# TTL_to_RS485_Converter_V1_1.net
KiCad netlist of a schematic drawn in EasyEDA Pro
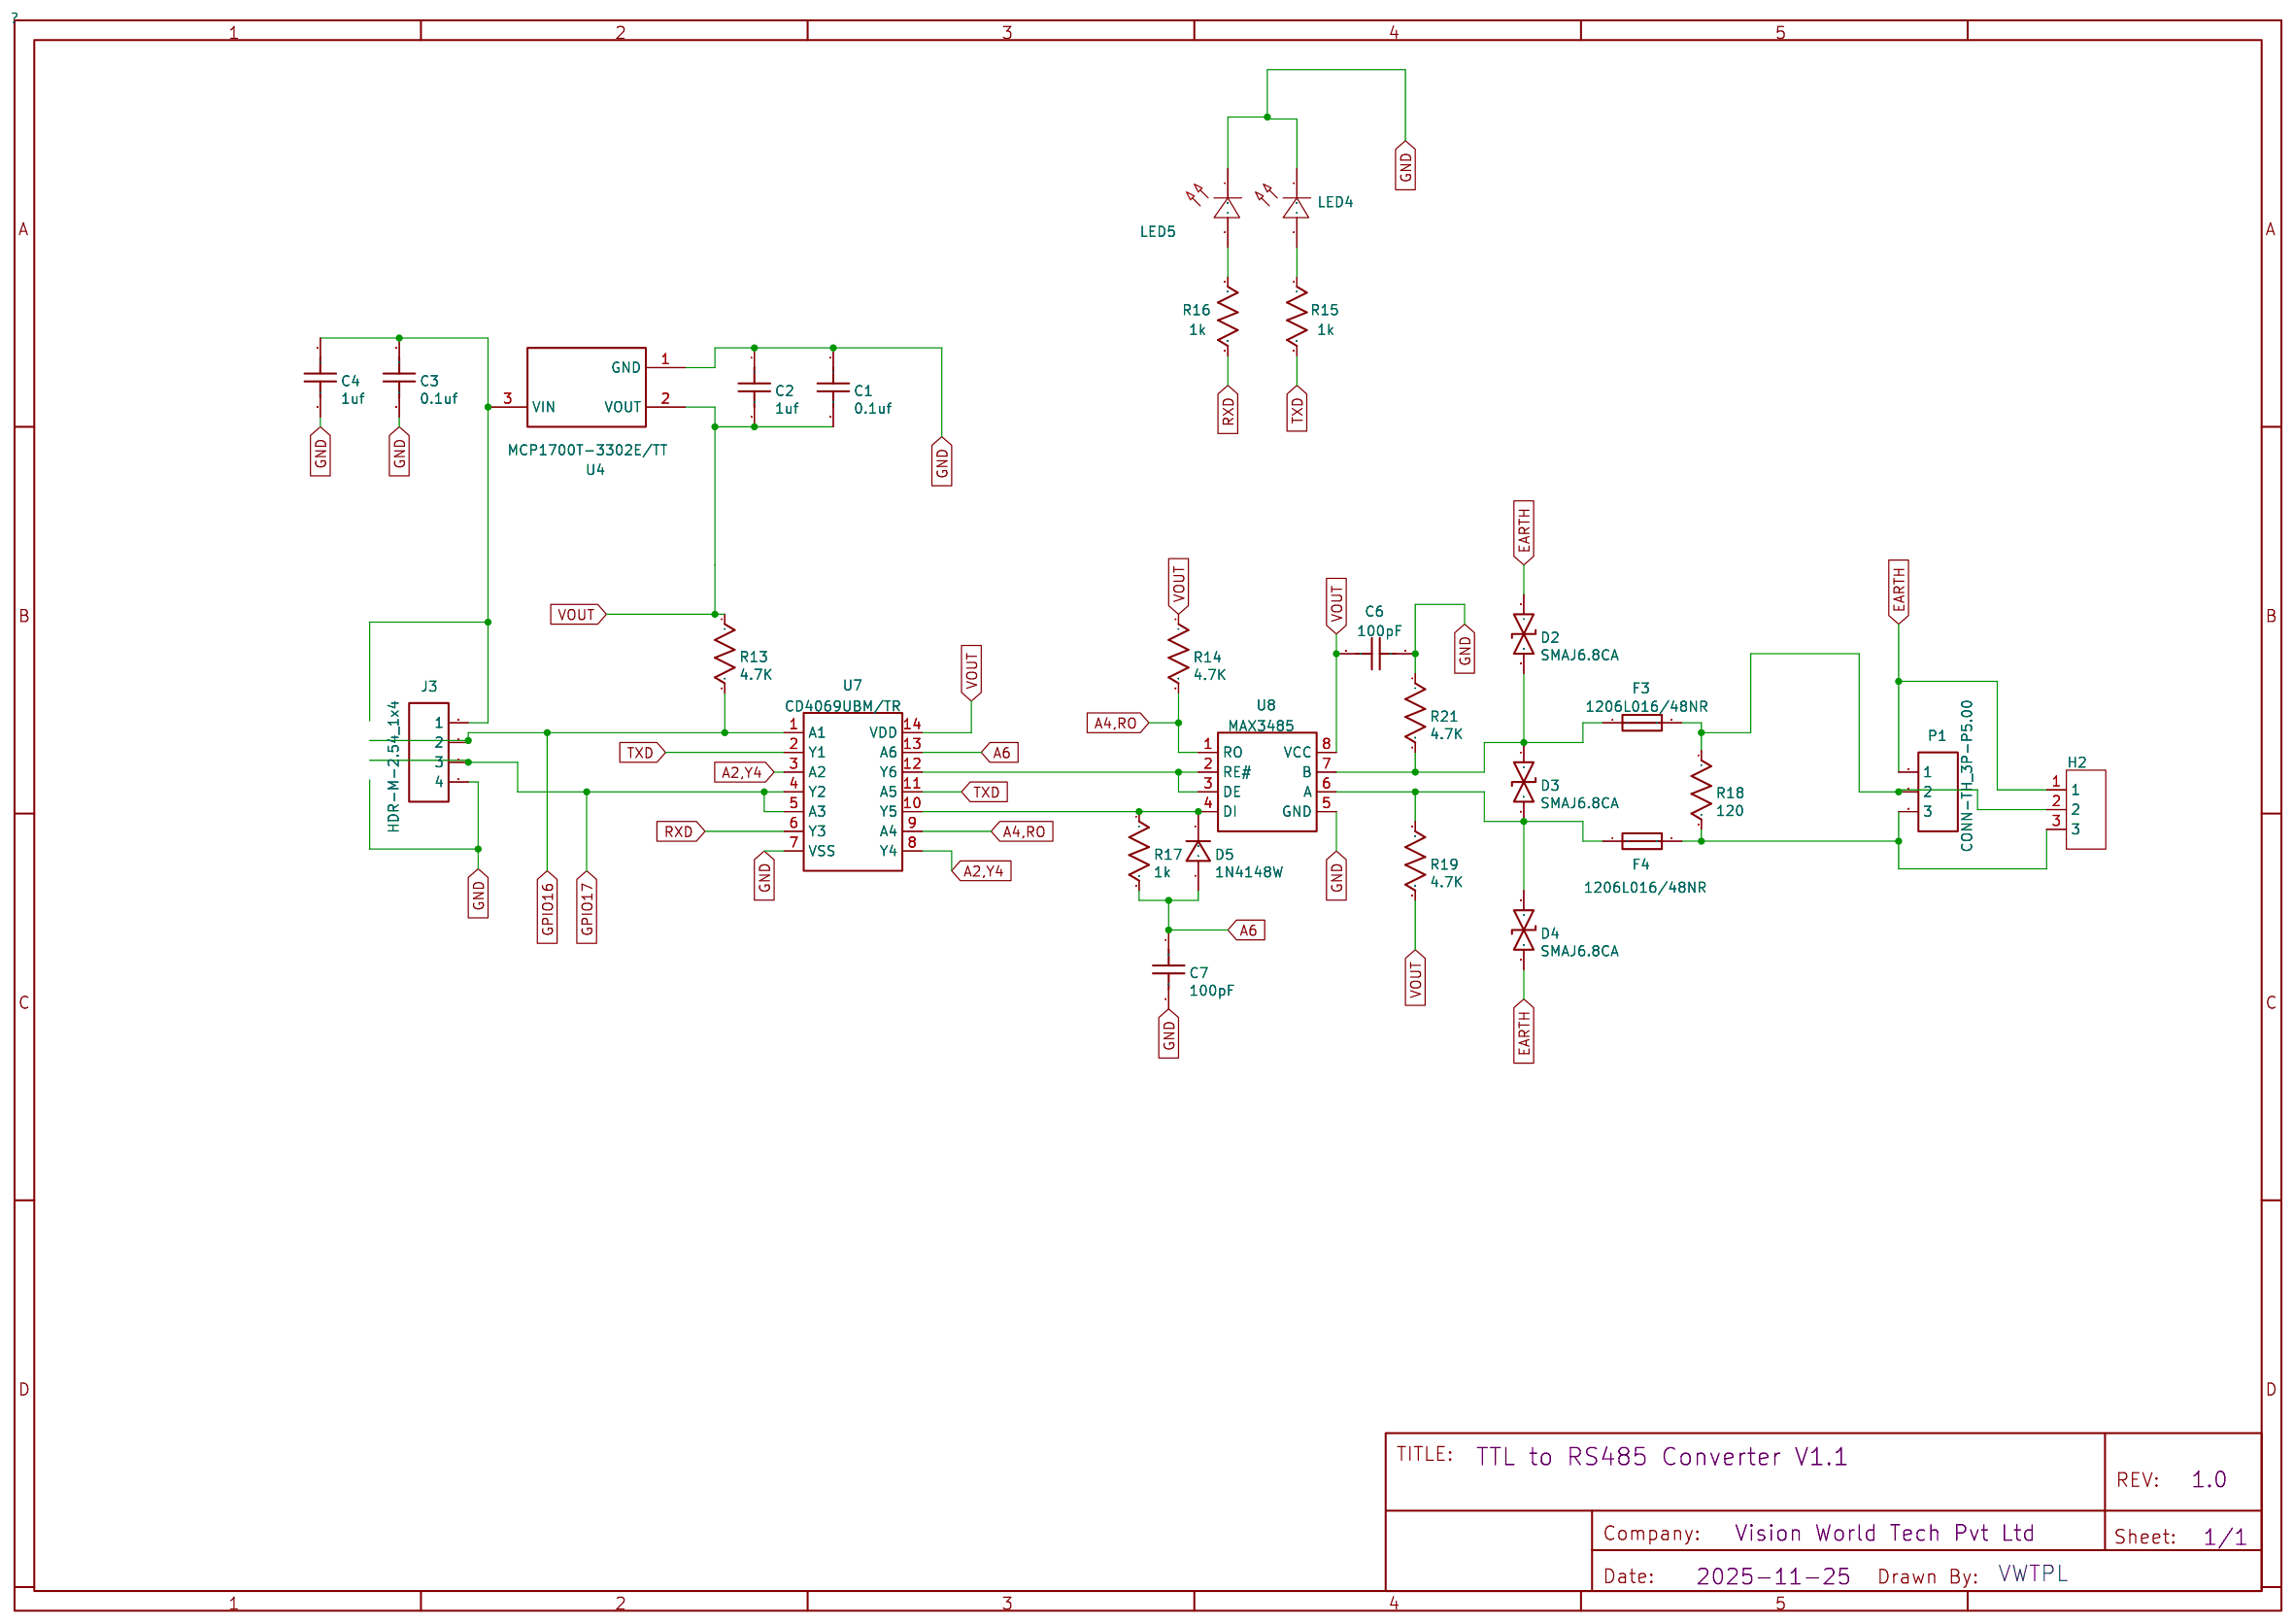
[diagram p0: schematic sheet]

(export (version "E")
  (design (tool "Eeschema 10.0.6"))
  (components
    (comp (ref "C1")
      (value "0.1uf")
      (footprint "easyedapro:C1206")
      (fields (field (name "Contributor") "LCEDA_Lib"))
      (libsource (lib "easyedapro") (part "0.1uf"))
    )
    (comp (ref "C2")
      (value "1uf")
      (footprint "easyedapro:C1206")
      (fields (field (name "Contributor") "LCEDA_Lib"))
      (libsource (lib "easyedapro") (part "1uf"))
    )
    (comp (ref "C3")
      (value "0.1uf")
      (footprint "easyedapro:C1206")
      (fields (field (name "Contributor") "LCEDA_Lib"))
      (libsource (lib "easyedapro") (part "0.1uf"))
    )
    (comp (ref "C4")
      (value "1uf")
      (footprint "easyedapro:C1206")
      (fields (field (name "Contributor") "LCEDA_Lib"))
      (libsource (lib "easyedapro") (part "1uf"))
    )
    (comp (ref "C6")
      (value "100pF")
      (footprint "easyedapro:C1206")
      (fields (field (name "Contributor") "LCEDA_Lib"))
      (libsource (lib "easyedapro") (part "100pF"))
    )
    (comp (ref "C7")
      (value "100pF")
      (footprint "easyedapro:C1206")
      (fields (field (name "Contributor") "LCEDA_Lib"))
      (libsource (lib "easyedapro") (part "100pF"))
    )
    (comp (ref "D2")
      (value "SMAJ6.8CA")
      (footprint "easyedapro:SMA_L4.4-W2.6-LS5.0-BI")
      (fields (field (name "Manufacturer") "BORN(伯恩半导体)") (field (name "Contributor") "LCSC"))
      (libsource (lib "easyedapro") (part "SMAJ6.8CA"))
    )
    (comp (ref "D3")
      (value "SMAJ6.8CA")
      (footprint "easyedapro:SMA_L4.4-W2.6-LS5.0-BI")
      (fields (field (name "Manufacturer") "BORN(伯恩半导体)") (field (name "Contributor") "LCSC"))
      (libsource (lib "easyedapro") (part "SMAJ6.8CA"))
    )
    (comp (ref "D4")
      (value "SMAJ6.8CA")
      (footprint "easyedapro:SMA_L4.4-W2.6-LS5.0-BI")
      (fields (field (name "Manufacturer") "BORN(伯恩半导体)") (field (name "Contributor") "LCSC"))
      (libsource (lib "easyedapro") (part "SMAJ6.8CA"))
    )
    (comp (ref "D5")
      (value "1N4148W")
      (footprint "easyedapro:SOD-123FL_L2.6-W1.6-LS3.4-RD")
      (fields (field (name "Manufacturer") "Tak Cheong") (field (name "Contributor") "LCEDA_Lib"))
      (libsource (lib "easyedapro") (part "1N4148W"))
    )
    (comp (ref "F3")
      (value "1206L016/48NR")
      (footprint "easyedapro:FUSE-SMD_1206L016-48NR")
      (fields (field (name "Manufacturer") "LUTE(陆特)") (field (name "Contributor") "lcsc"))
      (libsource (lib "easyedapro") (part "1206L016/48NR"))
    )
    (comp (ref "F4")
      (value "1206L016/48NR")
      (footprint "easyedapro:FUSE-SMD_1206L016-48NR")
      (fields (field (name "Manufacturer") "LUTE(陆特)") (field (name "Contributor") "lcsc"))
      (libsource (lib "easyedapro") (part "1206L016/48NR"))
    )
    (comp (ref "H2")
      (value "~")
      (footprint "easyedapro:HDR-TH_3P-P2.54-V-M")
      (libsource (lib "easyedapro") (part "PZ254V-11-03P_C2937625"))
    )
    (comp (ref "J3")
      (value "HDR-M-2.54_1x4")
      (footprint "easyedapro:HDR-M-2.54_1X4")
      (fields (field (name "Contributor") "LCEDA_Lib"))
      (libsource (lib "easyedapro") (part "HDR-M-2.54_1x4"))
    )
    (comp (ref "LED4")
      (value "~")
      (footprint "easyedapro:LED0805-RD_GREEN")
      (libsource (lib "easyedapro") (part "LED_B"))
    )
    (comp (ref "LED5")
      (value "~")
      (footprint "easyedapro:LED0805-RD_GREEN")
      (libsource (lib "easyedapro") (part "LED_G"))
    )
    (comp (ref "P1")
      (value "CONN-TH_3P-P5.00")
      (footprint "easyedapro:CONN-TH_3P-P5.00")
      (fields (field (name "Contributor") "LCEDA_Lib"))
      (libsource (lib "easyedapro") (part "CONN-TH_3P-P5.00"))
    )
    (comp (ref "R13")
      (value "4.7K")
      (footprint "easyedapro:R1206")
      (fields (field (name "Contributor") "LCEDA_Lib"))
      (libsource (lib "easyedapro") (part "4.7K"))
    )
    (comp (ref "R14")
      (value "4.7K")
      (footprint "easyedapro:R1206")
      (fields (field (name "Contributor") "LCEDA_Lib"))
      (libsource (lib "easyedapro") (part "4.7K"))
    )
    (comp (ref "R15")
      (value "1k")
      (footprint "easyedapro:R1206")
      (fields (field (name "Contributor") "LCEDA_Lib"))
      (libsource (lib "easyedapro") (part "1k"))
    )
    (comp (ref "R16")
      (value "1k")
      (footprint "easyedapro:R1206")
      (fields (field (name "Contributor") "LCEDA_Lib"))
      (libsource (lib "easyedapro") (part "1k"))
    )
    (comp (ref "R17")
      (value "1k")
      (footprint "easyedapro:R1206")
      (fields (field (name "Contributor") "LCEDA_Lib"))
      (libsource (lib "easyedapro") (part "1k"))
    )
    (comp (ref "R18")
      (value "120")
      (footprint "easyedapro:R1206")
      (fields (field (name "Contributor") "LCEDA_Lib"))
      (libsource (lib "easyedapro") (part "120"))
    )
    (comp (ref "R19")
      (value "4.7K")
      (footprint "easyedapro:R1206")
      (fields (field (name "Contributor") "LCEDA_Lib"))
      (libsource (lib "easyedapro") (part "4.7K"))
    )
    (comp (ref "R21")
      (value "4.7K")
      (footprint "easyedapro:R1206")
      (fields (field (name "Contributor") "LCEDA_Lib"))
      (libsource (lib "easyedapro") (part "4.7K"))
    )
    (comp (ref "U4")
      (value "MCP1700T-3302E/TT")
      (footprint "easyedapro:MCP1700-SOT-23-3_L2.9-W1.6-P1.90-LS2.8-BR")
      (fields (field (name "Manufacturer") "MICROCHIP") (field (name "Contributor") "Lavar Technologies"))
      (libsource (lib "easyedapro") (part "MCP1700T-3302E/TT"))
    )
    (comp (ref "U7")
      (value "CD4069UBM/TR")
      (footprint "easyedapro:SOIC-14_L8.7-W3.9-P1.27-LS6.0-BL")
      (fields (field (name "Manufacturer") "HGSEMI(华冠)") (field (name "Contributor") "LCSC"))
      (libsource (lib "easyedapro") (part "CD4069UBM/TR"))
    )
    (comp (ref "U8")
      (value "MAX3485")
      (footprint "easyedapro:SOP-8_L4.9-W3.9-P1.27-LS6.0-BL")
      (fields
        (field (name "Manufacturer Part") "MAX3485EIM/TR(ES)")
        (field (name "Manufacturer") "ElecSuper(静芯微)")
        (field (name "Contributor") "lcsc")
      )
      (libsource (lib "easyedapro") (part "MAX3485"))
    )
  )
  (nets
    (net (code "1") (name "A2,Y4") (class "Default")
      (node (ref "U7") (pin "3") (pinfunction "A2_3") (pintype "unspecified"))
      (node (ref "U7") (pin "8") (pinfunction "Y4_8") (pintype "unspecified"))
    )
    (net (code "2") (name "A4,RO") (class "Default")
      (node (ref "R14") (pin "2") (pinfunction "2_2") (pintype "unspecified"))
      (node (ref "U7") (pin "9") (pinfunction "A4_9") (pintype "unspecified"))
      (node (ref "U8") (pin "1") (pinfunction "RO_1") (pintype "unspecified"))
    )
    (net (code "3") (name "A6") (class "Default")
      (node (ref "C7") (pin "1") (pinfunction "1_1") (pintype "unspecified"))
      (node (ref "D5") (pin "2") (pinfunction "2_2") (pintype "unspecified"))
      (node (ref "R17") (pin "2") (pinfunction "2_2") (pintype "unspecified"))
      (node (ref "U7") (pin "13") (pinfunction "A6_13") (pintype "unspecified"))
    )
    (net (code "4") (name "EARTH") (class "Default")
      (node (ref "D2") (pin "1") (pinfunction "1_1") (pintype "unspecified"))
      (node (ref "D4") (pin "2") (pinfunction "2_2") (pintype "unspecified"))
      (node (ref "H2") (pin "1") (pinfunction "1_1") (pintype "unspecified"))
      (node (ref "P1") (pin "1") (pinfunction "1_1") (pintype "unspecified"))
    )
    (net (code "5") (name "GND") (class "Default")
      (node (ref "C1") (pin "1") (pinfunction "1_1") (pintype "unspecified"))
      (node (ref "C2") (pin "1") (pinfunction "1_1") (pintype "unspecified"))
      (node (ref "C3") (pin "2") (pinfunction "2_2") (pintype "unspecified"))
      (node (ref "C4") (pin "2") (pinfunction "2_2") (pintype "unspecified"))
      (node (ref "C6") (pin "1") (pinfunction "1_1") (pintype "unspecified"))
      (node (ref "C7") (pin "2") (pinfunction "2_2") (pintype "unspecified"))
      (node (ref "J3") (pin "4") (pinfunction "4_4") (pintype "unspecified"))
      (node (ref "LED4") (pin "1") (pinfunction "C_1") (pintype "input"))
      (node (ref "LED5") (pin "1") (pinfunction "C_1") (pintype "input"))
      (node (ref "R21") (pin "1") (pinfunction "1_1") (pintype "unspecified"))
      (node (ref "U4") (pin "1") (pinfunction "GND_1") (pintype "unspecified"))
      (node (ref "U7") (pin "7") (pinfunction "VSS_7") (pintype "unspecified"))
      (node (ref "U8") (pin "5") (pinfunction "GND_5") (pintype "unspecified"))
    )
    (net (code "6") (name "GPIO16") (class "Default")
      (node (ref "J3") (pin "2") (pinfunction "2_2") (pintype "unspecified"))
      (node (ref "R13") (pin "2") (pinfunction "2_2") (pintype "unspecified"))
      (node (ref "U7") (pin "1") (pinfunction "A1_1") (pintype "unspecified"))
    )
    (net (code "7") (name "GPIO17") (class "Default")
      (node (ref "J3") (pin "3") (pinfunction "3_3") (pintype "unspecified"))
      (node (ref "U7") (pin "4") (pinfunction "Y2_4") (pintype "unspecified"))
      (node (ref "U7") (pin "5") (pinfunction "A3_5") (pintype "unspecified"))
    )
    (net (code "8") (name "Net-(F3-Pad2)") (class "Default")
      (node (ref "F3") (pin "2") (pinfunction "2_2") (pintype "unspecified"))
      (node (ref "H2") (pin "2") (pinfunction "2_2") (pintype "unspecified"))
      (node (ref "P1") (pin "2") (pinfunction "2_2") (pintype "unspecified"))
      (node (ref "R18") (pin "1") (pinfunction "1_1") (pintype "unspecified"))
    )
    (net (code "9") (name "Net-(F4-Pad2)") (class "Default")
      (node (ref "F4") (pin "2") (pinfunction "2_2") (pintype "unspecified"))
      (node (ref "H2") (pin "3") (pinfunction "3_3") (pintype "unspecified"))
      (node (ref "P1") (pin "3") (pinfunction "3_3") (pintype "unspecified"))
      (node (ref "R18") (pin "2") (pinfunction "2_2") (pintype "unspecified"))
    )
    (net (code "10") (name "Net-(LED4-A)") (class "Default")
      (node (ref "LED4") (pin "2") (pinfunction "A_2") (pintype "input"))
      (node (ref "R15") (pin "1") (pinfunction "1_1") (pintype "unspecified"))
    )
    (net (code "11") (name "Net-(LED5-A)") (class "Default")
      (node (ref "LED5") (pin "2") (pinfunction "A_2") (pintype "input"))
      (node (ref "R16") (pin "1") (pinfunction "1_1") (pintype "unspecified"))
    )
    (net (code "12") (name "Net-(U4-VIN)") (class "Default")
      (node (ref "C3") (pin "1") (pinfunction "1_1") (pintype "unspecified"))
      (node (ref "C4") (pin "1") (pinfunction "1_1") (pintype "unspecified"))
      (node (ref "J3") (pin "1") (pinfunction "1_1") (pintype "unspecified"))
      (node (ref "U4") (pin "3") (pinfunction "VIN_3") (pintype "unspecified"))
    )
    (net (code "13") (name "Net-(U7-Y5)") (class "Default")
      (node (ref "D5") (pin "1") (pinfunction "1_1") (pintype "unspecified"))
      (node (ref "R17") (pin "1") (pinfunction "1_1") (pintype "unspecified"))
      (node (ref "U7") (pin "10") (pinfunction "Y5_10") (pintype "unspecified"))
      (node (ref "U8") (pin "4") (pinfunction "DI_4") (pintype "unspecified"))
    )
    (net (code "14") (name "Net-(U7-Y6)") (class "Default")
      (node (ref "U7") (pin "12") (pinfunction "Y6_12") (pintype "unspecified"))
      (node (ref "U8") (pin "2") (pinfunction "RE#_2") (pintype "unspecified"))
      (node (ref "U8") (pin "3") (pinfunction "DE_3") (pintype "unspecified"))
    )
    (net (code "15") (name "Net-(U8-A)") (class "Default")
      (node (ref "D3") (pin "2") (pinfunction "2_2") (pintype "unspecified"))
      (node (ref "D4") (pin "1") (pinfunction "1_1") (pintype "unspecified"))
      (node (ref "F4") (pin "1") (pinfunction "1_1") (pintype "unspecified"))
      (node (ref "R19") (pin "1") (pinfunction "1_1") (pintype "unspecified"))
      (node (ref "U8") (pin "6") (pinfunction "A_6") (pintype "unspecified"))
    )
    (net (code "16") (name "Net-(U8-B)") (class "Default")
      (node (ref "D2") (pin "2") (pinfunction "2_2") (pintype "unspecified"))
      (node (ref "D3") (pin "1") (pinfunction "1_1") (pintype "unspecified"))
      (node (ref "F3") (pin "1") (pinfunction "1_1") (pintype "unspecified"))
      (node (ref "R21") (pin "2") (pinfunction "2_2") (pintype "unspecified"))
      (node (ref "U8") (pin "7") (pinfunction "B_7") (pintype "unspecified"))
    )
    (net (code "17") (name "RXD") (class "Default")
      (node (ref "R16") (pin "2") (pinfunction "2_2") (pintype "unspecified"))
      (node (ref "U7") (pin "6") (pinfunction "Y3_6") (pintype "unspecified"))
    )
    (net (code "18") (name "TXD") (class "Default")
      (node (ref "R15") (pin "2") (pinfunction "2_2") (pintype "unspecified"))
      (node (ref "U7") (pin "11") (pinfunction "A5_11") (pintype "unspecified"))
      (node (ref "U7") (pin "2") (pinfunction "Y1_2") (pintype "unspecified"))
    )
    (net (code "19") (name "VOUT") (class "Default")
      (node (ref "C1") (pin "2") (pinfunction "2_2") (pintype "unspecified"))
      (node (ref "C2") (pin "2") (pinfunction "2_2") (pintype "unspecified"))
      (node (ref "C6") (pin "2") (pinfunction "2_2") (pintype "unspecified"))
      (node (ref "R13") (pin "1") (pinfunction "1_1") (pintype "unspecified"))
      (node (ref "R14") (pin "1") (pinfunction "1_1") (pintype "unspecified"))
      (node (ref "R19") (pin "2") (pinfunction "2_2") (pintype "unspecified"))
      (node (ref "U4") (pin "2") (pinfunction "VOUT_2") (pintype "unspecified"))
      (node (ref "U7") (pin "14") (pinfunction "VDD_14") (pintype "unspecified"))
      (node (ref "U8") (pin "8") (pinfunction "VCC_8") (pintype "unspecified"))
    )
  )
)
